# Schematic.net
KiCad netlist of a schematic drawn in Altium Designer
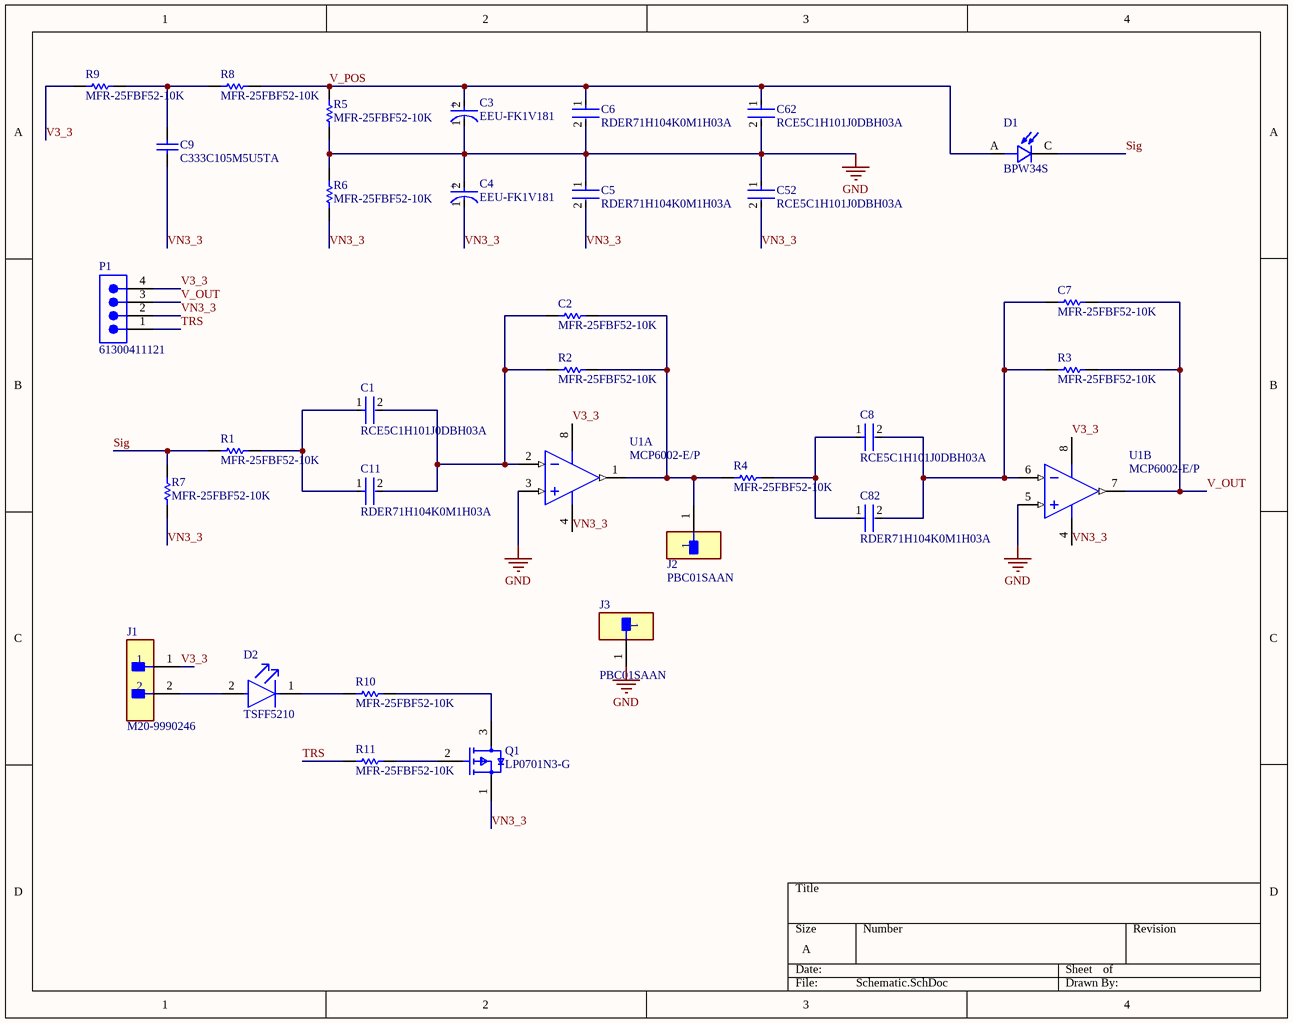
[diagram p0: Schematic.SchDoc]

(export (version "E")
  (design (tool "Eeschema 10.0.6"))
  (components
    (comp (ref "C1")
      (value "RCE5C1H101J0DBH03A")
      (footprint "FP-RCE0DB-MFG")
      (libsource (lib "Robert Harper") (part "b4654b650e69147ec39a6b967a45e02"))
    )
    (comp (ref "C2")
      (value "MFR-25FBF52-10K")
      (footprint "RESA60-630X240")
      (description "Fixed Resistor, Metal Film, 0.25W, 10000ohm, 250V, 1% +/-Tol, -100,100ppm/Cel")
      (fields (field (name "TOLERANCE") "1%") (field (name "POWER") "250mW"))
      (libsource (lib "Robert Harper") (part "RES-2"))
    )
    (comp (ref "C3")
      (value "EEU-FK1V181")
      (footprint "FP-RAD-TH-D_8_0_5-L_11_5-MFG")
      (libsource (lib "Robert Harper") (part "a00bbbee19879c290e62620ae7e47b1"))
    )
    (comp (ref "C4")
      (value "EEU-FK1V181")
      (footprint "FP-RAD-TH-D_8_0_5-L_11_5-MFG")
      (libsource (lib "Robert Harper") (part "a00bbbee19879c290e62620ae7e47b1"))
    )
    (comp (ref "C5")
      (value "RDER71H104K0M1H03A")
      (footprint "FP-RDE0M1-MFG")
      (libsource (lib "Robert Harper") (part "b4654b650e69147ec39a6b967a45e02"))
    )
    (comp (ref "C6")
      (value "RDER71H104K0M1H03A")
      (footprint "FP-RDE0M1-MFG")
      (libsource (lib "Robert Harper") (part "b4654b650e69147ec39a6b967a45e02"))
    )
    (comp (ref "C7")
      (value "MFR-25FBF52-10K")
      (footprint "RESA60-630X240")
      (description "Fixed Resistor, Metal Film, 0.25W, 10000ohm, 250V, 1% +/-Tol, -100,100ppm/Cel")
      (fields (field (name "TOLERANCE") "1%") (field (name "POWER") "250mW"))
      (libsource (lib "Robert Harper") (part "RES-2"))
    )
    (comp (ref "C8")
      (value "RCE5C1H101J0DBH03A")
      (footprint "FP-RCE0DB-MFG")
      (libsource (lib "Robert Harper") (part "b4654b650e69147ec39a6b967a45e02"))
    )
    (comp (ref "C9")
      (value "C333C105M5U5TA")
      (footprint "KEMT-C333C105M5U5TA-2")
      (libsource (lib "Robert Harper") (part "CAP-NP-2"))
    )
    (comp (ref "C11")
      (value "RDER71H104K0M1H03A")
      (footprint "FP-RDE0M1-MFG")
      (libsource (lib "Robert Harper") (part "b4654b650e69147ec39a6b967a45e02"))
    )
    (comp (ref "C52")
      (value "RCE5C1H101J0DBH03A")
      (footprint "FP-RCE0DB-MFG")
      (libsource (lib "Robert Harper") (part "b4654b650e69147ec39a6b967a45e02"))
    )
    (comp (ref "C62")
      (value "RCE5C1H101J0DBH03A")
      (footprint "FP-RCE0DB-MFG")
      (libsource (lib "Robert Harper") (part "b4654b650e69147ec39a6b967a45e02"))
    )
    (comp (ref "C82")
      (value "RDER71H104K0M1H03A")
      (footprint "FP-RDE0M1-MFG")
      (libsource (lib "Robert Harper") (part "b4654b650e69147ec39a6b967a45e02"))
    )
    (comp (ref "D1")
      (value "BPW34S")
      (footprint "DIO_BPW34S")
      (description "Photodiode 850nm 20ns 120Â° 2-SMD, Gull Wing")
      (fields (field (name "MF") "OSRAM Opto"))
      (libsource (lib "BPW34S") (part "BPW34S"))
    )
    (comp (ref "D2")
      (value "TSFF5210")
      (footprint "FP-6_544-5258_09-4-MFG")
      (description "Infrared LED, 5mm, 1-Element, 870nm")
      (libsource (lib "Robert Harper") (part "8706943c75ba83719d021d2fdc84c58"))
    )
    (comp (ref "J1")
      (value "M20-9990246")
      (footprint "FP-M20-9990246-MFG")
      (libsource (lib "Ethan Sorensen") (part "3bc925449376181038e59eaffc5286c"))
    )
    (comp (ref "J2")
      (value "PBC01SAAN")
      (footprint "FP-PBC01SAAN-MFG")
      (description "Board Connector, 1 Contact(s), 1 Row(s), Male, Straight, 0.1 inch Pitch, Solder Terminal")
      (libsource (lib "") (part "dd45045ce8184df9e99e12baf3f412c_1"))
    )
    (comp (ref "J3")
      (value "PBC01SAAN")
      (footprint "FP-PBC01SAAN-MFG")
      (description "Board Connector, 1 Contact(s), 1 Row(s), Male, Straight, 0.1 inch Pitch, Solder Terminal")
      (libsource (lib "Robert Harper") (part "dd45045ce8184df9e99e12baf3f412c"))
    )
    (comp (ref "P1")
      (value "61300411121")
      (footprint "61300411121")
      (libsource (lib "Robert Harper") (part "Header_Male_1R_04P"))
    )
    (comp (ref "Q1")
      (value "LP0701N3-G")
      (footprint "FP-N3-MFG")
      (description "Mosfet; P-channel Enhancement-mode; -16.5V; 1.5 OHM3 TO-92BAG")
      (libsource (lib "Robert Harper") (part "d53c4972c00c3379e0fba722f59b06f"))
    )
    (comp (ref "R1")
      (value "MFR-25FBF52-10K")
      (footprint "RESA60-630X240")
      (description "Fixed Resistor, Metal Film, 0.25W, 10000ohm, 250V, 1% +/-Tol, -100,100ppm/Cel")
      (fields (field (name "TOLERANCE") "1%") (field (name "POWER") "250mW"))
      (libsource (lib "Robert Harper") (part "RES-2"))
    )
    (comp (ref "R2")
      (value "MFR-25FBF52-10K")
      (footprint "RESA60-630X240")
      (description "Fixed Resistor, Metal Film, 0.25W, 10000ohm, 250V, 1% +/-Tol, -100,100ppm/Cel")
      (fields (field (name "TOLERANCE") "1%") (field (name "POWER") "250mW"))
      (libsource (lib "Robert Harper") (part "RES-2"))
    )
    (comp (ref "R3")
      (value "MFR-25FBF52-10K")
      (footprint "RESA60-630X240")
      (description "Fixed Resistor, Metal Film, 0.25W, 10000ohm, 250V, 1% +/-Tol, -100,100ppm/Cel")
      (fields (field (name "TOLERANCE") "1%") (field (name "POWER") "250mW"))
      (libsource (lib "Robert Harper") (part "RES-2"))
    )
    (comp (ref "R4")
      (value "MFR-25FBF52-10K")
      (footprint "RESA60-630X240")
      (description "Fixed Resistor, Metal Film, 0.25W, 10000ohm, 250V, 1% +/-Tol, -100,100ppm/Cel")
      (fields (field (name "TOLERANCE") "1%") (field (name "POWER") "250mW"))
      (libsource (lib "Robert Harper") (part "RES-2"))
    )
    (comp (ref "R5")
      (value "MFR-25FBF52-10K")
      (footprint "RESA60-630X240")
      (description "Fixed Resistor, Metal Film, 0.25W, 10000ohm, 250V, 1% +/-Tol, -100,100ppm/Cel")
      (fields (field (name "TOLERANCE") "1%") (field (name "POWER") "250mW"))
      (libsource (lib "Robert Harper") (part "RES-2"))
    )
    (comp (ref "R6")
      (value "MFR-25FBF52-10K")
      (footprint "RESA60-630X240")
      (description "Fixed Resistor, Metal Film, 0.25W, 10000ohm, 250V, 1% +/-Tol, -100,100ppm/Cel")
      (fields (field (name "TOLERANCE") "1%") (field (name "POWER") "250mW"))
      (libsource (lib "Robert Harper") (part "RES-2"))
    )
    (comp (ref "R7")
      (value "MFR-25FBF52-10K")
      (footprint "RESA60-630X240")
      (description "Fixed Resistor, Metal Film, 0.25W, 10000ohm, 250V, 1% +/-Tol, -100,100ppm/Cel")
      (fields (field (name "TOLERANCE") "1%") (field (name "POWER") "250mW"))
      (libsource (lib "Robert Harper") (part "RES-2"))
    )
    (comp (ref "R8")
      (value "MFR-25FBF52-10K")
      (footprint "RESA60-630X240")
      (description "Fixed Resistor, Metal Film, 0.25W, 10000ohm, 250V, 1% +/-Tol, -100,100ppm/Cel")
      (fields (field (name "TOLERANCE") "1%") (field (name "POWER") "250mW"))
      (libsource (lib "Robert Harper") (part "RES-2"))
    )
    (comp (ref "R9")
      (value "MFR-25FBF52-10K")
      (footprint "RESA60-630X240")
      (description "Fixed Resistor, Metal Film, 0.25W, 10000ohm, 250V, 1% +/-Tol, -100,100ppm/Cel")
      (fields (field (name "TOLERANCE") "1%") (field (name "POWER") "250mW"))
      (libsource (lib "Robert Harper") (part "RES-2"))
    )
    (comp (ref "R10")
      (value "MFR-25FBF52-10K")
      (footprint "RESA60-630X240")
      (description "Fixed Resistor, Metal Film, 0.25W, 10000ohm, 250V, 1% +/-Tol, -100,100ppm/Cel")
      (fields (field (name "TOLERANCE") "1%") (field (name "POWER") "250mW"))
      (libsource (lib "Robert Harper") (part "RES-2"))
    )
    (comp (ref "R11")
      (value "MFR-25FBF52-10K")
      (footprint "RESA60-630X240")
      (description "Fixed Resistor, Metal Film, 0.25W, 10000ohm, 250V, 1% +/-Tol, -100,100ppm/Cel")
      (fields (field (name "TOLERANCE") "1%") (field (name "POWER") "250mW"))
      (libsource (lib "Robert Harper") (part "RES-2"))
    )
    (comp (ref "U1")
      (value "MCP6002-E/P")
      (footprint "PDIP300-P8")
      (description "Operational Amplifier, 2 Func, 4500uV Offset-Max, CMOS, PDIP8")
      (fields (field (name "POWER") "No"))
      (libsource (lib "Robert Harper") (part "AMP-OPA-MCP6002-IL8"))
    )
  )
  (nets
    (net (code "1") (name "/Sig") (class "Default")
      (node (ref "D1") (pin "C") (pinfunction "C_C") (pintype "passive"))
      (node (ref "R1") (pin "1") (pinfunction "1_1") (pintype "passive"))
      (node (ref "R7") (pin "2") (pinfunction "2_2") (pintype "passive"))
    )
    (net (code "2") (name "/TRS") (class "Default")
      (node (ref "P1") (pin "1") (pinfunction "1_1") (pintype "passive"))
      (node (ref "R11") (pin "1") (pinfunction "1_1") (pintype "passive"))
    )
    (net (code "3") (name "/V3_3") (class "Default")
      (node (ref "J1") (pin "1") (pinfunction "1_1") (pintype "passive"))
      (node (ref "P1") (pin "4") (pinfunction "4_4") (pintype "passive"))
      (node (ref "R9") (pin "1") (pinfunction "1_1") (pintype "passive"))
      (node (ref "U1") (pin "8") (pinfunction "VDD_8") (pintype "power_in"))
    )
    (net (code "4") (name "/VN3_3") (class "Default")
      (node (ref "C4") (pin "1") (pinfunction "C_1") (pintype "passive"))
      (node (ref "C5") (pin "2") (pinfunction "2_2") (pintype "passive"))
      (node (ref "C52") (pin "2") (pinfunction "2_2") (pintype "passive"))
      (node (ref "C9") (pin "1") (pinfunction "1_1") (pintype "passive"))
      (node (ref "P1") (pin "2") (pinfunction "2_2") (pintype "passive"))
      (node (ref "Q1") (pin "1") (pinfunction "S_1") (pintype "passive"))
      (node (ref "R6") (pin "1") (pinfunction "1_1") (pintype "passive"))
      (node (ref "R7") (pin "1") (pinfunction "1_1") (pintype "passive"))
      (node (ref "U1") (pin "4") (pinfunction "VSS_4") (pintype "power_in"))
    )
    (net (code "5") (name "/V_OUT") (class "Default")
      (node (ref "C7") (pin "2") (pinfunction "2_2") (pintype "passive"))
      (node (ref "P1") (pin "3") (pinfunction "3_3") (pintype "passive"))
      (node (ref "R3") (pin "2") (pinfunction "2_2") (pintype "passive"))
      (node (ref "U1") (pin "7") (pinfunction "VOUTB_7") (pintype "output"))
    )
    (net (code "6") (name "/V_POS") (class "Default")
      (node (ref "C3") (pin "2") (pinfunction "A_2") (pintype "passive"))
      (node (ref "C6") (pin "1") (pinfunction "1_1") (pintype "passive"))
      (node (ref "C62") (pin "1") (pinfunction "1_1") (pintype "passive"))
      (node (ref "D1") (pin "A") (pinfunction "A_A") (pintype "passive"))
      (node (ref "R5") (pin "2") (pinfunction "2_2") (pintype "passive"))
      (node (ref "R8") (pin "2") (pinfunction "2_2") (pintype "passive"))
    )
    (net (code "7") (name "GND") (class "Default")
      (node (ref "C3") (pin "1") (pinfunction "C_1") (pintype "passive"))
      (node (ref "C4") (pin "2") (pinfunction "A_2") (pintype "passive"))
      (node (ref "C5") (pin "1") (pinfunction "1_1") (pintype "passive"))
      (node (ref "C52") (pin "1") (pinfunction "1_1") (pintype "passive"))
      (node (ref "C6") (pin "2") (pinfunction "2_2") (pintype "passive"))
      (node (ref "C62") (pin "2") (pinfunction "2_2") (pintype "passive"))
      (node (ref "J3") (pin "1") (pinfunction "1_1") (pintype "passive"))
      (node (ref "R5") (pin "1") (pinfunction "1_1") (pintype "passive"))
      (node (ref "R6") (pin "2") (pinfunction "2_2") (pintype "passive"))
      (node (ref "U1") (pin "3") (pinfunction "VINA+_3") (pintype "input"))
      (node (ref "U1") (pin "5") (pinfunction "VINB+_5") (pintype "input"))
    )
    (net (code "8") (name "Net-(C1-Pad1)") (class "Default")
      (node (ref "C1") (pin "1") (pinfunction "1_1") (pintype "passive"))
      (node (ref "C11") (pin "1") (pinfunction "1_1") (pintype "passive"))
      (node (ref "R1") (pin "2") (pinfunction "2_2") (pintype "passive"))
    )
    (net (code "9") (name "Net-(C8-Pad1)") (class "Default")
      (node (ref "C8") (pin "1") (pinfunction "1_1") (pintype "passive"))
      (node (ref "C82") (pin "1") (pinfunction "1_1") (pintype "passive"))
      (node (ref "R4") (pin "2") (pinfunction "2_2") (pintype "passive"))
    )
    (net (code "10") (name "Net-(C9-Pad2)") (class "Default")
      (node (ref "C9") (pin "2") (pinfunction "2_2") (pintype "passive"))
      (node (ref "R8") (pin "1") (pinfunction "1_1") (pintype "passive"))
      (node (ref "R9") (pin "2") (pinfunction "2_2") (pintype "passive"))
    )
    (net (code "11") (name "Net-(D2-A)") (class "Default")
      (node (ref "D2") (pin "2") (pinfunction "A_2") (pintype "passive"))
      (node (ref "J1") (pin "2") (pinfunction "2_2") (pintype "passive"))
    )
    (net (code "12") (name "Net-(D2-C)") (class "Default")
      (node (ref "D2") (pin "1") (pinfunction "C_1") (pintype "passive"))
      (node (ref "R10") (pin "1") (pinfunction "1_1") (pintype "passive"))
    )
    (net (code "13") (name "Net-(Q1-D)") (class "Default")
      (node (ref "Q1") (pin "3") (pinfunction "D_3") (pintype "passive"))
      (node (ref "R10") (pin "2") (pinfunction "2_2") (pintype "passive"))
    )
    (net (code "14") (name "Net-(Q1-G)") (class "Default")
      (node (ref "Q1") (pin "2") (pinfunction "G_2") (pintype "passive"))
      (node (ref "R11") (pin "2") (pinfunction "2_2") (pintype "passive"))
    )
    (net (code "15") (name "Net-(U1A-VINA-)") (class "Default")
      (node (ref "C1") (pin "2") (pinfunction "2_2") (pintype "passive"))
      (node (ref "C11") (pin "2") (pinfunction "2_2") (pintype "passive"))
      (node (ref "C2") (pin "1") (pinfunction "1_1") (pintype "passive"))
      (node (ref "R2") (pin "1") (pinfunction "1_1") (pintype "passive"))
      (node (ref "U1") (pin "2") (pinfunction "VINA-_2") (pintype "input"))
    )
    (net (code "16") (name "Net-(U1A-VOUTA)") (class "Default")
      (node (ref "C2") (pin "2") (pinfunction "2_2") (pintype "passive"))
      (node (ref "J2") (pin "1") (pinfunction "1_1") (pintype "passive"))
      (node (ref "R2") (pin "2") (pinfunction "2_2") (pintype "passive"))
      (node (ref "R4") (pin "1") (pinfunction "1_1") (pintype "passive"))
      (node (ref "U1") (pin "1") (pinfunction "VOUTA_1") (pintype "output"))
    )
    (net (code "17") (name "Net-(U1B-VINB-)") (class "Default")
      (node (ref "C7") (pin "1") (pinfunction "1_1") (pintype "passive"))
      (node (ref "C8") (pin "2") (pinfunction "2_2") (pintype "passive"))
      (node (ref "C82") (pin "2") (pinfunction "2_2") (pintype "passive"))
      (node (ref "R3") (pin "1") (pinfunction "1_1") (pintype "passive"))
      (node (ref "U1") (pin "6") (pinfunction "VINB-_6") (pintype "input"))
    )
  )
)
